# 457_I2S_Stereo_Sound_Rev020000beta.net
KiCad netlist of a schematic drawn in EAGLE
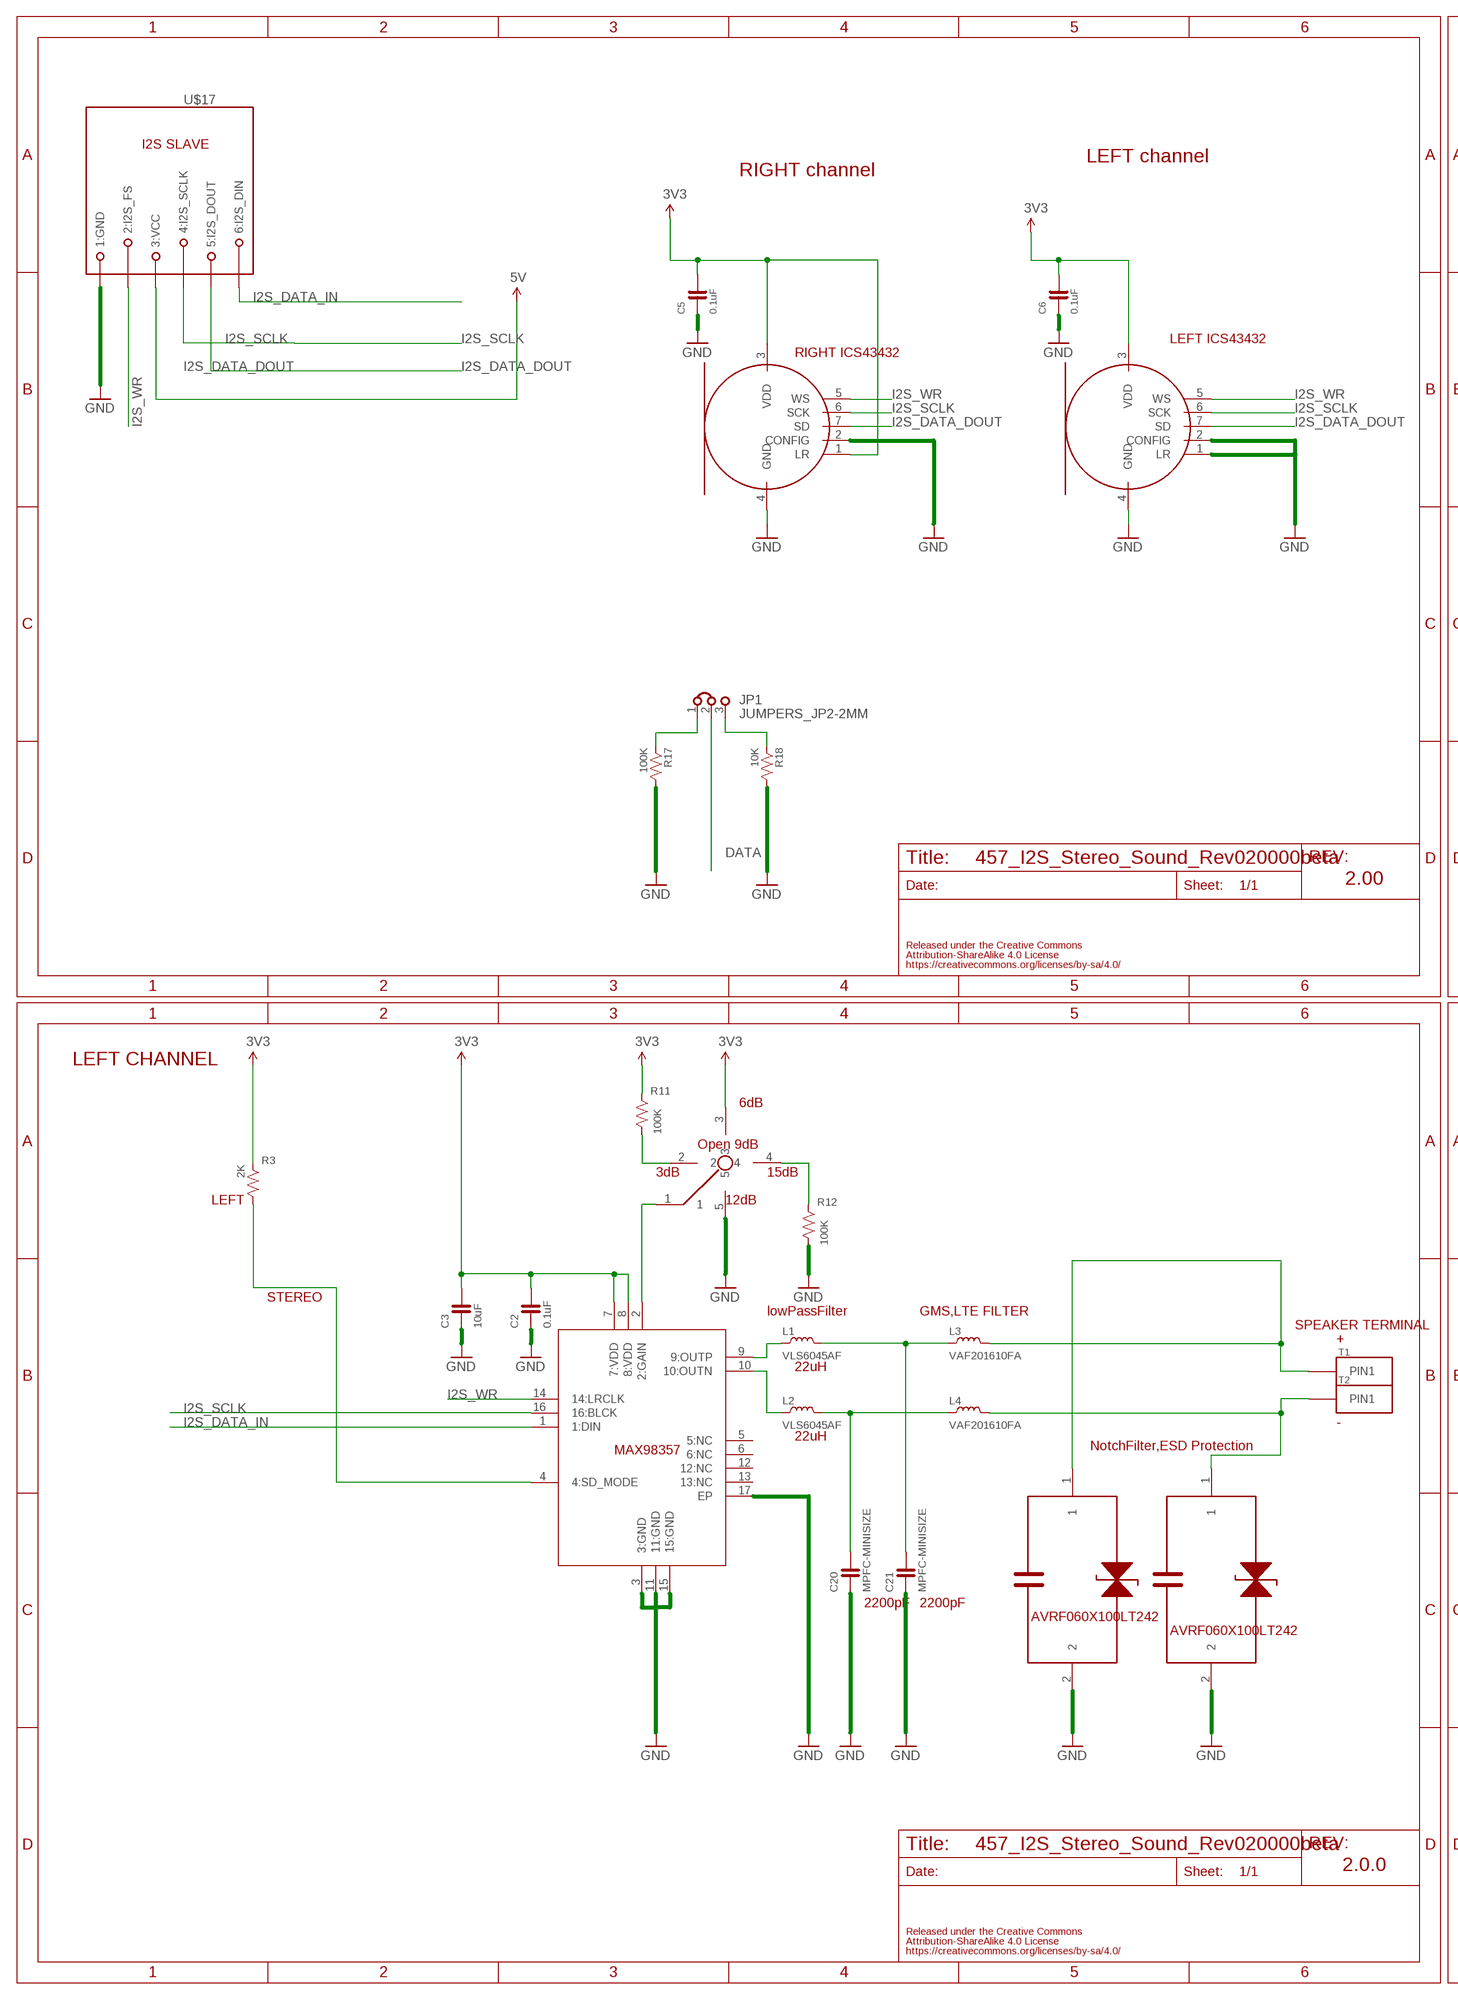
[diagram p0: schematic, sheet 1, part 1 of 2]
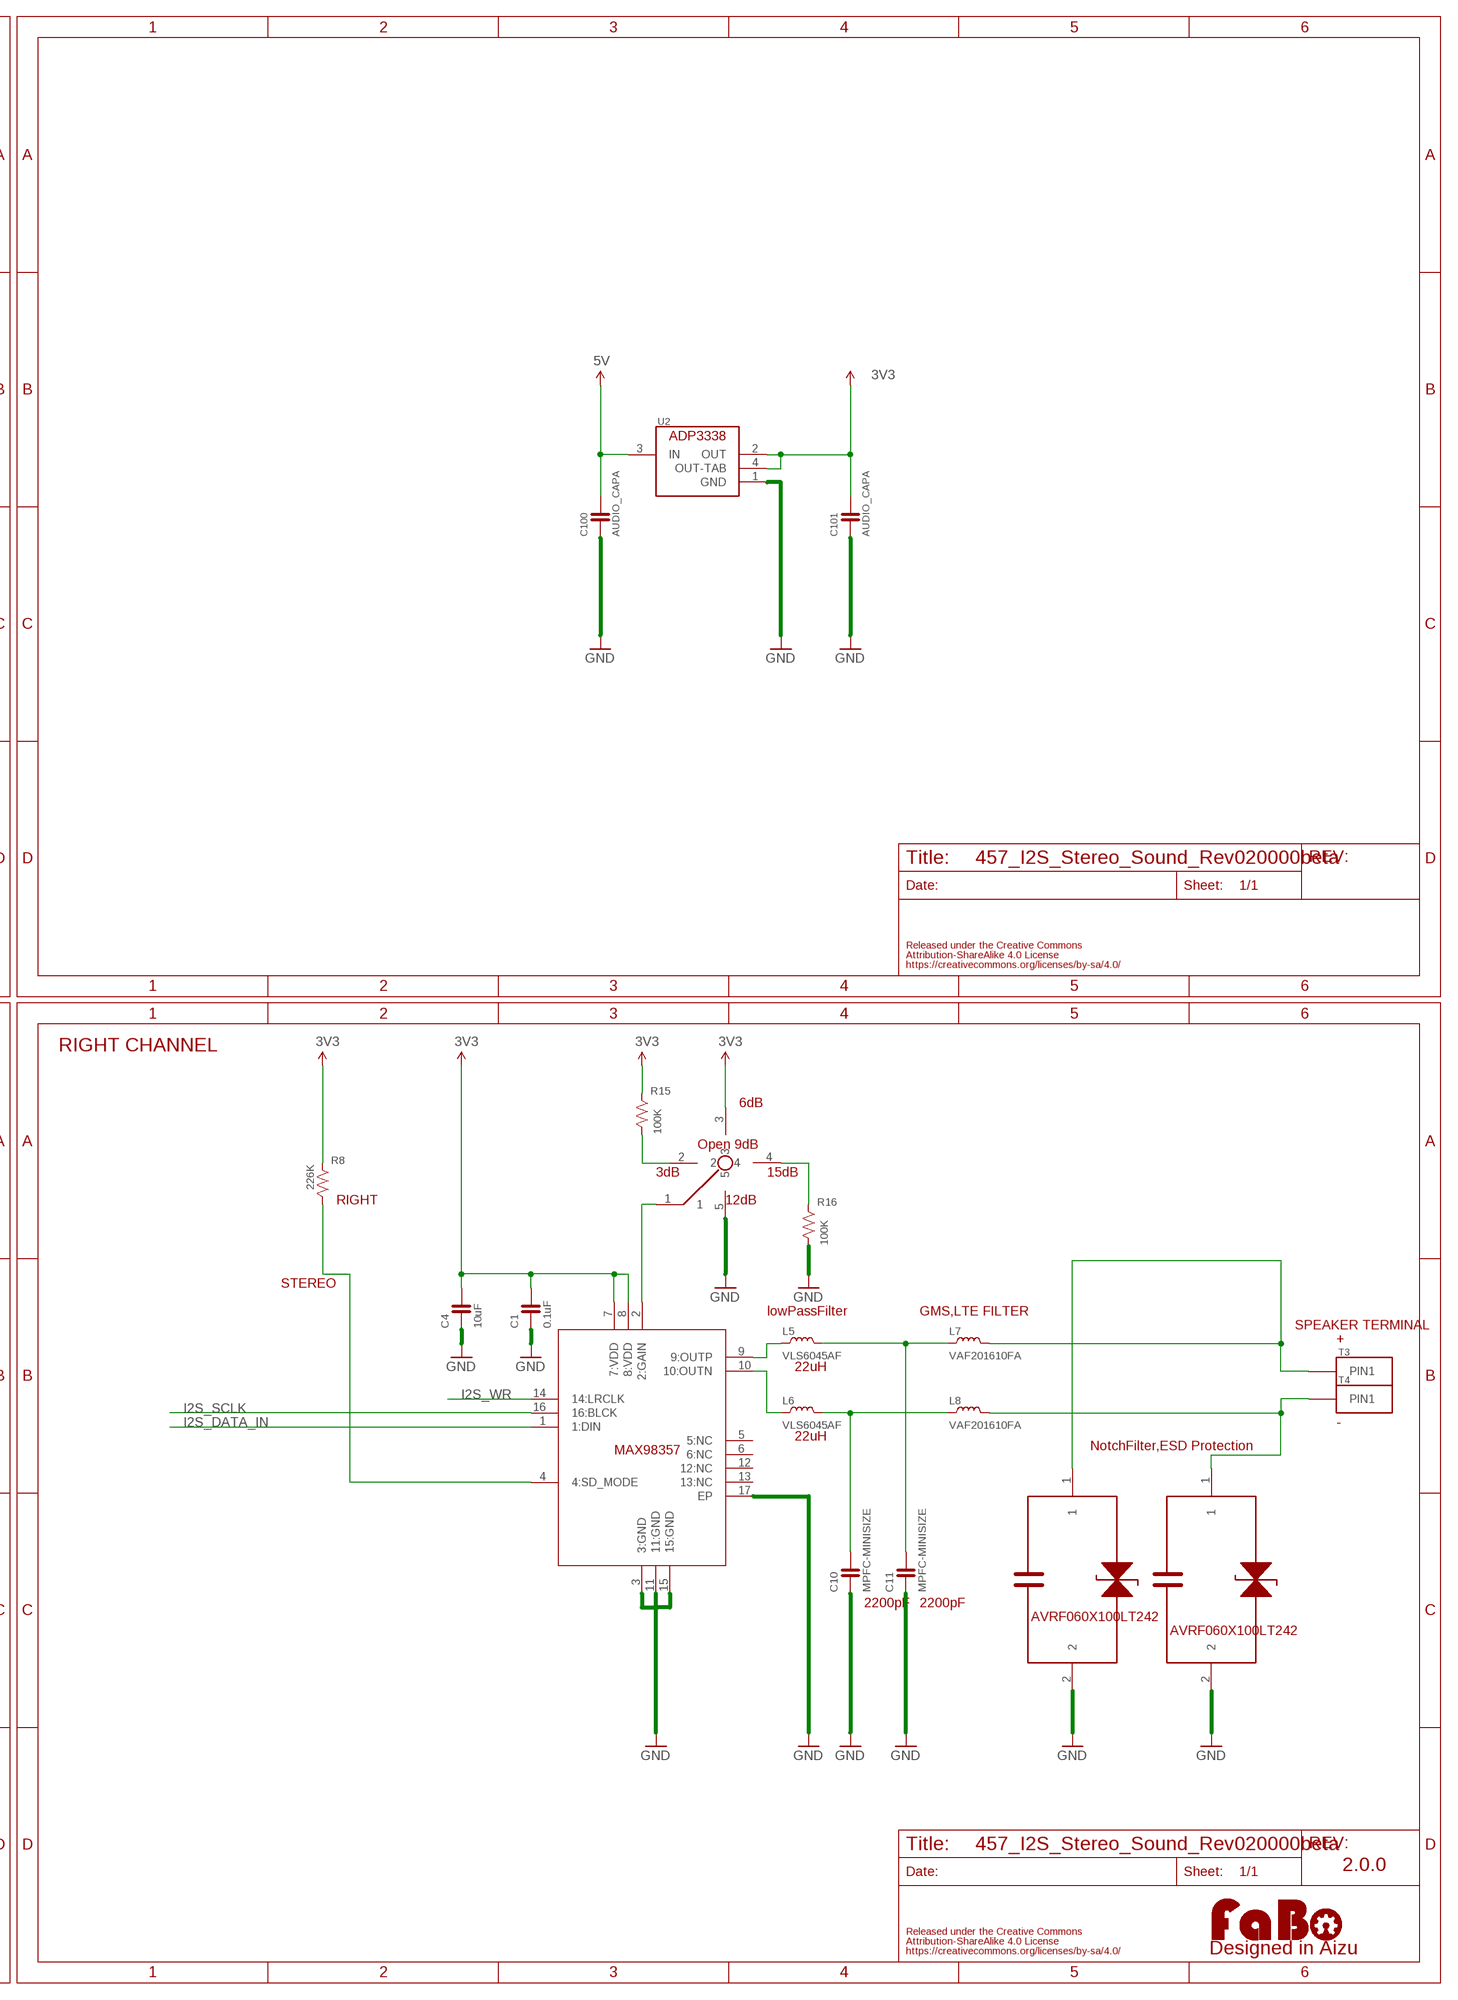
[diagram p1: schematic, sheet 1, part 2 of 2]

(export (version "E")
  (design (tool "Eeschema 10.0.6"))
  (components
    (comp (ref "C1")
      (value "0.1uF")
      (footprint "eagle-import:0603")
      (libsource (lib "eagle-import") (part "CAPACITOR-0603"))
    )
    (comp (ref "C2")
      (value "0.1uF")
      (footprint "eagle-import:0603")
      (libsource (lib "eagle-import") (part "CAPACITOR-0603"))
    )
    (comp (ref "C3")
      (value "10uF")
      (footprint "eagle-import:0603")
      (libsource (lib "eagle-import") (part "CAPACITOR-0603"))
    )
    (comp (ref "C4")
      (value "10uF")
      (footprint "eagle-import:0603")
      (libsource (lib "eagle-import") (part "CAPACITOR-0603"))
    )
    (comp (ref "C5")
      (value "0.1uF")
      (footprint "eagle-import:0402")
      (libsource (lib "eagle-import") (part "CAPACITOR-0402"))
    )
    (comp (ref "C6")
      (value "0.1uF")
      (footprint "eagle-import:0402")
      (libsource (lib "eagle-import") (part "CAPACITOR-0402"))
    )
    (comp (ref "C10")
      (value "MPFC-MINISIZE")
      (footprint "eagle-import:DIP-MPFC")
      (libsource (lib "eagle-import") (part "MPFC-MINISIZE"))
    )
    (comp (ref "C11")
      (value "MPFC-MINISIZE")
      (footprint "eagle-import:DIP-MPFC")
      (libsource (lib "eagle-import") (part "MPFC-MINISIZE"))
    )
    (comp (ref "C20")
      (value "MPFC-MINISIZE")
      (footprint "eagle-import:DIP-MPFC")
      (libsource (lib "eagle-import") (part "MPFC-MINISIZE"))
    )
    (comp (ref "C21")
      (value "MPFC-MINISIZE")
      (footprint "eagle-import:DIP-MPFC")
      (libsource (lib "eagle-import") (part "MPFC-MINISIZE"))
    )
    (comp (ref "C100")
      (value "AUDIO_CAPA")
      (footprint "eagle-import:3216")
      (libsource (lib "eagle-import") (part "AUDIO_CAPA"))
    )
    (comp (ref "C101")
      (value "AUDIO_CAPA")
      (footprint "eagle-import:3216")
      (libsource (lib "eagle-import") (part "AUDIO_CAPA"))
    )
    (comp (ref "JP1")
      (value "JUMPERS_JP2-2MM")
      (footprint "eagle-import:JUMPERS_JP2-2MM")
      (libsource (lib "eagle-import") (part "JUMPERS_JP2-2MM"))
    )
    (comp (ref "L1")
      (value "VLS6045AF")
      (footprint "eagle-import:VLS6045AF")
      (libsource (lib "eagle-import") (part "VLS6045AF"))
    )
    (comp (ref "L2")
      (value "VLS6045AF")
      (footprint "eagle-import:VLS6045AF")
      (libsource (lib "eagle-import") (part "VLS6045AF"))
    )
    (comp (ref "L3")
      (value "VAF201610FA")
      (footprint "eagle-import:VAF201610FA-1")
      (libsource (lib "eagle-import") (part "VAF201610FA"))
    )
    (comp (ref "L4")
      (value "VAF201610FA")
      (footprint "eagle-import:VAF201610FA-1")
      (libsource (lib "eagle-import") (part "VAF201610FA"))
    )
    (comp (ref "L5")
      (value "VLS6045AF")
      (footprint "eagle-import:VLS6045AF")
      (libsource (lib "eagle-import") (part "VLS6045AF"))
    )
    (comp (ref "L6")
      (value "VLS6045AF")
      (footprint "eagle-import:VLS6045AF")
      (libsource (lib "eagle-import") (part "VLS6045AF"))
    )
    (comp (ref "L7")
      (value "VAF201610FA")
      (footprint "eagle-import:VAF201610FA-1")
      (libsource (lib "eagle-import") (part "VAF201610FA"))
    )
    (comp (ref "L8")
      (value "VAF201610FA")
      (footprint "eagle-import:VAF201610FA-1")
      (libsource (lib "eagle-import") (part "VAF201610FA"))
    )
    (comp (ref "LEFTAMP")
      (value "MAX98357A,B")
      (footprint "eagle-import:TQFN(16L3_3_0.75)")
      (libsource (lib "eagle-import") (part "MAX98357A,B"))
    )
    (comp (ref "LOGO1")
      (value "LOGO_FABO-M")
      (footprint "eagle-import:LOGO_FABO_M")
      (libsource (lib "eagle-import") (part "LOGO_FABO-M"))
    )
    (comp (ref "MIC_LEFT")
      (value "TDK-ICS43432")
      (footprint "eagle-import:TDK-ICS43432")
      (libsource (lib "eagle-import") (part "TDK-ICS43432"))
    )
    (comp (ref "MIC_RIGHT")
      (value "TDK-ICS43432")
      (footprint "eagle-import:TDK-ICS43432")
      (libsource (lib "eagle-import") (part "TDK-ICS43432"))
    )
    (comp (ref "R3")
      (value "2K")
      (footprint "eagle-import:0603")
      (libsource (lib "eagle-import") (part "RESISTOR-0603"))
    )
    (comp (ref "R8")
      (value "226K")
      (footprint "eagle-import:0603")
      (libsource (lib "eagle-import") (part "RESISTOR-0603"))
    )
    (comp (ref "R11")
      (value "100K")
      (footprint "eagle-import:0603")
      (libsource (lib "eagle-import") (part "RESISTOR-0603"))
    )
    (comp (ref "R12")
      (value "100K")
      (footprint "eagle-import:0603")
      (libsource (lib "eagle-import") (part "RESISTOR-0603"))
    )
    (comp (ref "R15")
      (value "100K")
      (footprint "eagle-import:0603")
      (libsource (lib "eagle-import") (part "RESISTOR-0603"))
    )
    (comp (ref "R16")
      (value "100K")
      (footprint "eagle-import:0603")
      (libsource (lib "eagle-import") (part "RESISTOR-0603"))
    )
    (comp (ref "R17")
      (value "100K")
      (footprint "eagle-import:0603")
      (libsource (lib "eagle-import") (part "RESISTOR-0603"))
    )
    (comp (ref "R18")
      (value "10K")
      (footprint "eagle-import:0603")
      (libsource (lib "eagle-import") (part "RESISTOR-0603"))
    )
    (comp (ref "RIGHTAMP")
      (value "MAX98357A,B")
      (footprint "eagle-import:TQFN(16L3_3_0.75)")
      (libsource (lib "eagle-import") (part "MAX98357A,B"))
    )
    (comp (ref "T1")
      (value "TBL004-508")
      (footprint "eagle-import:TBL004-508")
      (libsource (lib "eagle-import") (part "TBL004-508"))
    )
    (comp (ref "T2")
      (value "TBL004-508")
      (footprint "eagle-import:TBL004-508")
      (libsource (lib "eagle-import") (part "TBL004-508"))
    )
    (comp (ref "T3")
      (value "TBL004-508")
      (footprint "eagle-import:TBL004-508")
      (libsource (lib "eagle-import") (part "TBL004-508"))
    )
    (comp (ref "T4")
      (value "TBL004-508")
      (footprint "eagle-import:TBL004-508")
      (libsource (lib "eagle-import") (part "TBL004-508"))
    )
    (comp (ref "U$5")
      (value "AVRF060X100LT242")
      (footprint "eagle-import:AVRF0X0X100LT_0603")
      (libsource (lib "eagle-import") (part "AVRF060X100LT242"))
    )
    (comp (ref "U$7")
      (value "AVRF060X100LT242")
      (footprint "eagle-import:AVRF0X0X100LT_0603")
      (libsource (lib "eagle-import") (part "AVRF060X100LT242"))
    )
    (comp (ref "U$9")
      (value "AVRF060X100LT242")
      (footprint "eagle-import:AVRF0X0X100LT_0603")
      (libsource (lib "eagle-import") (part "AVRF060X100LT242"))
    )
    (comp (ref "U$11")
      (value "AVRF060X100LT242")
      (footprint "eagle-import:AVRF0X0X100LT_0603")
      (libsource (lib "eagle-import") (part "AVRF060X100LT242"))
    )
    (comp (ref "U$13")
      (value "2MMJUMPER_CROSS")
      (footprint "eagle-import:PINHEAD2MM_CROSS")
      (libsource (lib "eagle-import") (part "2MMJUMPER_CROSS"))
    )
    (comp (ref "U$14")
      (value "2MMJUMPER_CROSS")
      (footprint "eagle-import:PINHEAD2MM_CROSS")
      (libsource (lib "eagle-import") (part "2MMJUMPER_CROSS"))
    )
    (comp (ref "U$17")
      (value "MODULAR-JACK-6P-RJ11_I2S_SLAVE")
      (footprint "eagle-import:7002-6PXC-X")
      (libsource (lib "eagle-import") (part "MODULAR-JACK-6P-RJ11_I2S_SLAVE"))
    )
    (comp (ref "U2")
      (value "ADP3338AKCZ")
      (footprint "eagle-import:SOT-223-KC3")
      (libsource (lib "eagle-import") (part "ADP3338AKCZ"))
    )
  )
  (nets
    (net (code "1") (name "/DATA") (class "Default")
      (node (ref "JP1") (pin "2") (pinfunction "2_2") (pintype "passive"))
    )
    (net (code "2") (name "/I2S_DATA_DOUT") (class "Default")
      (node (ref "MIC_LEFT") (pin "7") (pinfunction "SD_7") (pintype "bidirectional"))
      (node (ref "MIC_RIGHT") (pin "7") (pinfunction "SD_7") (pintype "bidirectional"))
      (node (ref "U$17") (pin "5") (pinfunction "5:I2S_DOUT_5") (pintype "output"))
    )
    (net (code "3") (name "/I2S_DATA_IN") (class "Default")
      (node (ref "LEFTAMP") (pin "1") (pinfunction "1:DIN_1") (pintype "bidirectional"))
      (node (ref "RIGHTAMP") (pin "1") (pinfunction "1:DIN_1") (pintype "bidirectional"))
      (node (ref "U$17") (pin "6") (pinfunction "6:I2S_DIN_6") (pintype "input"))
    )
    (net (code "4") (name "/I2S_SCLK") (class "Default")
      (node (ref "LEFTAMP") (pin "16") (pinfunction "16:BLCK_16") (pintype "bidirectional"))
      (node (ref "MIC_LEFT") (pin "6") (pinfunction "SCK_6") (pintype "bidirectional"))
      (node (ref "MIC_RIGHT") (pin "6") (pinfunction "SCK_6") (pintype "bidirectional"))
      (node (ref "RIGHTAMP") (pin "16") (pinfunction "16:BLCK_16") (pintype "bidirectional"))
      (node (ref "U$17") (pin "4") (pinfunction "4:I2S_SCLK_4") (pintype "bidirectional"))
    )
    (net (code "5") (name "/I2S_WR") (class "Default")
      (node (ref "LEFTAMP") (pin "14") (pinfunction "14:LRCLK_14") (pintype "bidirectional"))
      (node (ref "MIC_LEFT") (pin "5") (pinfunction "WS_5") (pintype "bidirectional"))
      (node (ref "MIC_RIGHT") (pin "5") (pinfunction "WS_5") (pintype "bidirectional"))
      (node (ref "RIGHTAMP") (pin "14") (pinfunction "14:LRCLK_14") (pintype "bidirectional"))
      (node (ref "U$17") (pin "2") (pinfunction "2:I2S_FS_2") (pintype "bidirectional"))
    )
    (net (code "6") (name "3V3") (class "Default")
      (node (ref "C1") (pin "2") (pinfunction "2_2") (pintype "passive"))
      (node (ref "C101") (pin "2") (pinfunction "2_2") (pintype "passive"))
      (node (ref "C2") (pin "2") (pinfunction "2_2") (pintype "passive"))
      (node (ref "C3") (pin "2") (pinfunction "2_2") (pintype "passive"))
      (node (ref "C4") (pin "2") (pinfunction "2_2") (pintype "passive"))
      (node (ref "C5") (pin "2") (pinfunction "2_2") (pintype "passive"))
      (node (ref "C6") (pin "2") (pinfunction "2_2") (pintype "passive"))
      (node (ref "LEFTAMP") (pin "7") (pinfunction "7:VDD_7") (pintype "bidirectional"))
      (node (ref "LEFTAMP") (pin "8") (pinfunction "8:VDD_8") (pintype "bidirectional"))
      (node (ref "MIC_LEFT") (pin "3") (pinfunction "VDD_3") (pintype "bidirectional"))
      (node (ref "MIC_RIGHT") (pin "1") (pinfunction "LR_1") (pintype "bidirectional"))
      (node (ref "MIC_RIGHT") (pin "3") (pinfunction "VDD_3") (pintype "bidirectional"))
      (node (ref "R11") (pin "1") (pinfunction "1_1") (pintype "bidirectional"))
      (node (ref "R15") (pin "1") (pinfunction "1_1") (pintype "bidirectional"))
      (node (ref "R3") (pin "1") (pinfunction "1_1") (pintype "bidirectional"))
      (node (ref "R8") (pin "1") (pinfunction "1_1") (pintype "bidirectional"))
      (node (ref "RIGHTAMP") (pin "7") (pinfunction "7:VDD_7") (pintype "bidirectional"))
      (node (ref "RIGHTAMP") (pin "8") (pinfunction "8:VDD_8") (pintype "bidirectional"))
      (node (ref "U$13") (pin "3") (pinfunction "3_3") (pintype "bidirectional"))
      (node (ref "U$14") (pin "3") (pinfunction "3_3") (pintype "bidirectional"))
      (node (ref "U2") (pin "2") (pinfunction "OUT_2") (pintype "bidirectional"))
      (node (ref "U2") (pin "4") (pinfunction "OUT-TAB_4") (pintype "bidirectional"))
    )
    (net (code "7") (name "5V") (class "Default")
      (node (ref "C100") (pin "2") (pinfunction "2_2") (pintype "passive"))
      (node (ref "U$17") (pin "3") (pinfunction "3:VCC_3") (pintype "power_in"))
      (node (ref "U2") (pin "3") (pinfunction "IN_3") (pintype "bidirectional"))
    )
    (net (code "8") (name "GND") (class "Default")
      (node (ref "C1") (pin "1") (pinfunction "1_1") (pintype "passive"))
      (node (ref "C10") (pin "1") (pinfunction "1_1") (pintype "passive"))
      (node (ref "C100") (pin "1") (pinfunction "1_1") (pintype "passive"))
      (node (ref "C101") (pin "1") (pinfunction "1_1") (pintype "passive"))
      (node (ref "C11") (pin "1") (pinfunction "1_1") (pintype "passive"))
      (node (ref "C2") (pin "1") (pinfunction "1_1") (pintype "passive"))
      (node (ref "C20") (pin "1") (pinfunction "1_1") (pintype "passive"))
      (node (ref "C21") (pin "1") (pinfunction "1_1") (pintype "passive"))
      (node (ref "C3") (pin "1") (pinfunction "1_1") (pintype "passive"))
      (node (ref "C4") (pin "1") (pinfunction "1_1") (pintype "passive"))
      (node (ref "C5") (pin "1") (pinfunction "1_1") (pintype "passive"))
      (node (ref "C6") (pin "1") (pinfunction "1_1") (pintype "passive"))
      (node (ref "LEFTAMP") (pin "11") (pinfunction "11:GND_11") (pintype "bidirectional"))
      (node (ref "LEFTAMP") (pin "15") (pinfunction "15:GND_15") (pintype "bidirectional"))
      (node (ref "LEFTAMP") (pin "17") (pinfunction "EP_17") (pintype "bidirectional"))
      (node (ref "LEFTAMP") (pin "3") (pinfunction "3:GND_3") (pintype "bidirectional"))
      (node (ref "MIC_LEFT") (pin "1") (pinfunction "LR_1") (pintype "bidirectional"))
      (node (ref "MIC_LEFT") (pin "2") (pinfunction "CONFIG_2") (pintype "bidirectional"))
      (node (ref "MIC_LEFT") (pin "4") (pinfunction "GND_4") (pintype "bidirectional"))
      (node (ref "MIC_RIGHT") (pin "2") (pinfunction "CONFIG_2") (pintype "bidirectional"))
      (node (ref "MIC_RIGHT") (pin "4") (pinfunction "GND_4") (pintype "bidirectional"))
      (node (ref "R12") (pin "2") (pinfunction "2_2") (pintype "bidirectional"))
      (node (ref "R16") (pin "2") (pinfunction "2_2") (pintype "bidirectional"))
      (node (ref "R17") (pin "2") (pinfunction "2_2") (pintype "bidirectional"))
      (node (ref "R18") (pin "2") (pinfunction "2_2") (pintype "bidirectional"))
      (node (ref "RIGHTAMP") (pin "11") (pinfunction "11:GND_11") (pintype "bidirectional"))
      (node (ref "RIGHTAMP") (pin "15") (pinfunction "15:GND_15") (pintype "bidirectional"))
      (node (ref "RIGHTAMP") (pin "17") (pinfunction "EP_17") (pintype "bidirectional"))
      (node (ref "RIGHTAMP") (pin "3") (pinfunction "3:GND_3") (pintype "bidirectional"))
      (node (ref "U$11") (pin "2") (pinfunction "2_2") (pintype "bidirectional"))
      (node (ref "U$13") (pin "5") (pinfunction "5_5") (pintype "bidirectional"))
      (node (ref "U$14") (pin "5") (pinfunction "5_5") (pintype "bidirectional"))
      (node (ref "U$17") (pin "1") (pinfunction "1:GND_1") (pintype "power_in"))
      (node (ref "U$5") (pin "2") (pinfunction "2_2") (pintype "bidirectional"))
      (node (ref "U$7") (pin "2") (pinfunction "2_2") (pintype "bidirectional"))
      (node (ref "U$9") (pin "2") (pinfunction "2_2") (pintype "bidirectional"))
      (node (ref "U2") (pin "1") (pinfunction "GND_1") (pintype "bidirectional"))
    )
    (net (code "9") (name "Net-(C10-Pad2)") (class "Default")
      (node (ref "C10") (pin "2") (pinfunction "2_2") (pintype "passive"))
      (node (ref "L6") (pin "2") (pinfunction "2_2") (pintype "bidirectional"))
      (node (ref "L8") (pin "1") (pinfunction "1_1") (pintype "bidirectional"))
    )
    (net (code "10") (name "Net-(C11-Pad2)") (class "Default")
      (node (ref "C11") (pin "2") (pinfunction "2_2") (pintype "passive"))
      (node (ref "L5") (pin "2") (pinfunction "2_2") (pintype "bidirectional"))
      (node (ref "L7") (pin "1") (pinfunction "1_1") (pintype "bidirectional"))
    )
    (net (code "11") (name "Net-(C20-Pad2)") (class "Default")
      (node (ref "C20") (pin "2") (pinfunction "2_2") (pintype "passive"))
      (node (ref "L2") (pin "2") (pinfunction "2_2") (pintype "bidirectional"))
      (node (ref "L4") (pin "1") (pinfunction "1_1") (pintype "bidirectional"))
    )
    (net (code "12") (name "Net-(C21-Pad2)") (class "Default")
      (node (ref "C21") (pin "2") (pinfunction "2_2") (pintype "passive"))
      (node (ref "L1") (pin "2") (pinfunction "2_2") (pintype "bidirectional"))
      (node (ref "L3") (pin "1") (pinfunction "1_1") (pintype "bidirectional"))
    )
    (net (code "13") (name "Net-(JP1-Pad1)") (class "Default")
      (node (ref "JP1") (pin "1") (pinfunction "1_1") (pintype "passive"))
      (node (ref "R17") (pin "1") (pinfunction "1_1") (pintype "bidirectional"))
    )
    (net (code "14") (name "Net-(JP1-Pad3)") (class "Default")
      (node (ref "JP1") (pin "3") (pinfunction "3_3") (pintype "passive"))
      (node (ref "R18") (pin "1") (pinfunction "1_1") (pintype "bidirectional"))
    )
    (net (code "15") (name "Net-(L3-Pad2)") (class "Default")
      (node (ref "L3") (pin "2") (pinfunction "2_2") (pintype "bidirectional"))
      (node (ref "T1") (pin "P$1") (pinfunction "PIN1_P$1") (pintype "bidirectional"))
      (node (ref "T1") (pin "P$2") (pinfunction "PIN1_P$2") (pintype "bidirectional"))
      (node (ref "U$9") (pin "1") (pinfunction "1_1") (pintype "bidirectional"))
    )
    (net (code "16") (name "Net-(L4-Pad2)") (class "Default")
      (node (ref "L4") (pin "2") (pinfunction "2_2") (pintype "bidirectional"))
      (node (ref "T2") (pin "P$1") (pinfunction "PIN1_P$1") (pintype "bidirectional"))
      (node (ref "T2") (pin "P$2") (pinfunction "PIN1_P$2") (pintype "bidirectional"))
      (node (ref "U$11") (pin "1") (pinfunction "1_1") (pintype "bidirectional"))
    )
    (net (code "17") (name "Net-(L7-Pad2)") (class "Default")
      (node (ref "L7") (pin "2") (pinfunction "2_2") (pintype "bidirectional"))
      (node (ref "T3") (pin "P$1") (pinfunction "PIN1_P$1") (pintype "bidirectional"))
      (node (ref "T3") (pin "P$2") (pinfunction "PIN1_P$2") (pintype "bidirectional"))
      (node (ref "U$5") (pin "1") (pinfunction "1_1") (pintype "bidirectional"))
    )
    (net (code "18") (name "Net-(L8-Pad2)") (class "Default")
      (node (ref "L8") (pin "2") (pinfunction "2_2") (pintype "bidirectional"))
      (node (ref "T4") (pin "P$1") (pinfunction "PIN1_P$1") (pintype "bidirectional"))
      (node (ref "T4") (pin "P$2") (pinfunction "PIN1_P$2") (pintype "bidirectional"))
      (node (ref "U$7") (pin "1") (pinfunction "1_1") (pintype "bidirectional"))
    )
    (net (code "19") (name "Net-(LEFTAMP-2:GAIN)") (class "Default")
      (node (ref "LEFTAMP") (pin "2") (pinfunction "2:GAIN_2") (pintype "bidirectional"))
      (node (ref "U$13") (pin "1") (pinfunction "1_1") (pintype "bidirectional"))
    )
    (net (code "20") (name "Net-(LEFTAMP-4:SD_MODE)") (class "Default")
      (node (ref "LEFTAMP") (pin "4") (pinfunction "4:SD_MODE_4") (pintype "bidirectional"))
      (node (ref "R3") (pin "2") (pinfunction "2_2") (pintype "bidirectional"))
    )
    (net (code "21") (name "Net-(LEFTAMP-9:OUTP)") (class "Default")
      (node (ref "L1") (pin "1") (pinfunction "1_1") (pintype "bidirectional"))
      (node (ref "LEFTAMP") (pin "9") (pinfunction "9:OUTP_9") (pintype "bidirectional"))
    )
    (net (code "22") (name "Net-(LEFTAMP-10:OUTN)") (class "Default")
      (node (ref "L2") (pin "1") (pinfunction "1_1") (pintype "bidirectional"))
      (node (ref "LEFTAMP") (pin "10") (pinfunction "10:OUTN_10") (pintype "bidirectional"))
    )
    (net (code "23") (name "Net-(R11-Pad2)") (class "Default")
      (node (ref "R11") (pin "2") (pinfunction "2_2") (pintype "bidirectional"))
      (node (ref "U$13") (pin "2") (pinfunction "2_2") (pintype "bidirectional"))
    )
    (net (code "24") (name "Net-(R12-Pad1)") (class "Default")
      (node (ref "R12") (pin "1") (pinfunction "1_1") (pintype "bidirectional"))
      (node (ref "U$13") (pin "4") (pinfunction "4_4") (pintype "bidirectional"))
    )
    (net (code "25") (name "Net-(R15-Pad2)") (class "Default")
      (node (ref "R15") (pin "2") (pinfunction "2_2") (pintype "bidirectional"))
      (node (ref "U$14") (pin "2") (pinfunction "2_2") (pintype "bidirectional"))
    )
    (net (code "26") (name "Net-(R16-Pad1)") (class "Default")
      (node (ref "R16") (pin "1") (pinfunction "1_1") (pintype "bidirectional"))
      (node (ref "U$14") (pin "4") (pinfunction "4_4") (pintype "bidirectional"))
    )
    (net (code "27") (name "Net-(RIGHTAMP-2:GAIN)") (class "Default")
      (node (ref "RIGHTAMP") (pin "2") (pinfunction "2:GAIN_2") (pintype "bidirectional"))
      (node (ref "U$14") (pin "1") (pinfunction "1_1") (pintype "bidirectional"))
    )
    (net (code "28") (name "Net-(RIGHTAMP-4:SD_MODE)") (class "Default")
      (node (ref "R8") (pin "2") (pinfunction "2_2") (pintype "bidirectional"))
      (node (ref "RIGHTAMP") (pin "4") (pinfunction "4:SD_MODE_4") (pintype "bidirectional"))
    )
    (net (code "29") (name "Net-(RIGHTAMP-9:OUTP)") (class "Default")
      (node (ref "L5") (pin "1") (pinfunction "1_1") (pintype "bidirectional"))
      (node (ref "RIGHTAMP") (pin "9") (pinfunction "9:OUTP_9") (pintype "bidirectional"))
    )
    (net (code "30") (name "Net-(RIGHTAMP-10:OUTN)") (class "Default")
      (node (ref "L6") (pin "1") (pinfunction "1_1") (pintype "bidirectional"))
      (node (ref "RIGHTAMP") (pin "10") (pinfunction "10:OUTN_10") (pintype "bidirectional"))
    )
    (net (code "31") (name "unconnected-(LEFTAMP-5:NC-Pad5)") (class "Default")
      (node (ref "LEFTAMP") (pin "5") (pinfunction "5:NC_5") (pintype "no_connect"))
    )
    (net (code "32") (name "unconnected-(LEFTAMP-6:NC-Pad6)") (class "Default")
      (node (ref "LEFTAMP") (pin "6") (pinfunction "6:NC_6") (pintype "no_connect"))
    )
    (net (code "33") (name "unconnected-(LEFTAMP-12:NC-Pad12)") (class "Default")
      (node (ref "LEFTAMP") (pin "12") (pinfunction "12:NC_12") (pintype "no_connect"))
    )
    (net (code "34") (name "unconnected-(LEFTAMP-13:NC-Pad13)") (class "Default")
      (node (ref "LEFTAMP") (pin "13") (pinfunction "13:NC_13") (pintype "no_connect"))
    )
    (net (code "35") (name "unconnected-(RIGHTAMP-5:NC-Pad5)") (class "Default")
      (node (ref "RIGHTAMP") (pin "5") (pinfunction "5:NC_5") (pintype "no_connect"))
    )
    (net (code "36") (name "unconnected-(RIGHTAMP-6:NC-Pad6)") (class "Default")
      (node (ref "RIGHTAMP") (pin "6") (pinfunction "6:NC_6") (pintype "no_connect"))
    )
    (net (code "37") (name "unconnected-(RIGHTAMP-12:NC-Pad12)") (class "Default")
      (node (ref "RIGHTAMP") (pin "12") (pinfunction "12:NC_12") (pintype "no_connect"))
    )
    (net (code "38") (name "unconnected-(RIGHTAMP-13:NC-Pad13)") (class "Default")
      (node (ref "RIGHTAMP") (pin "13") (pinfunction "13:NC_13") (pintype "no_connect"))
    )
  )
)
